# Switches_Leds.net
KiCad netlist of a schematic drawn in Altium Designer
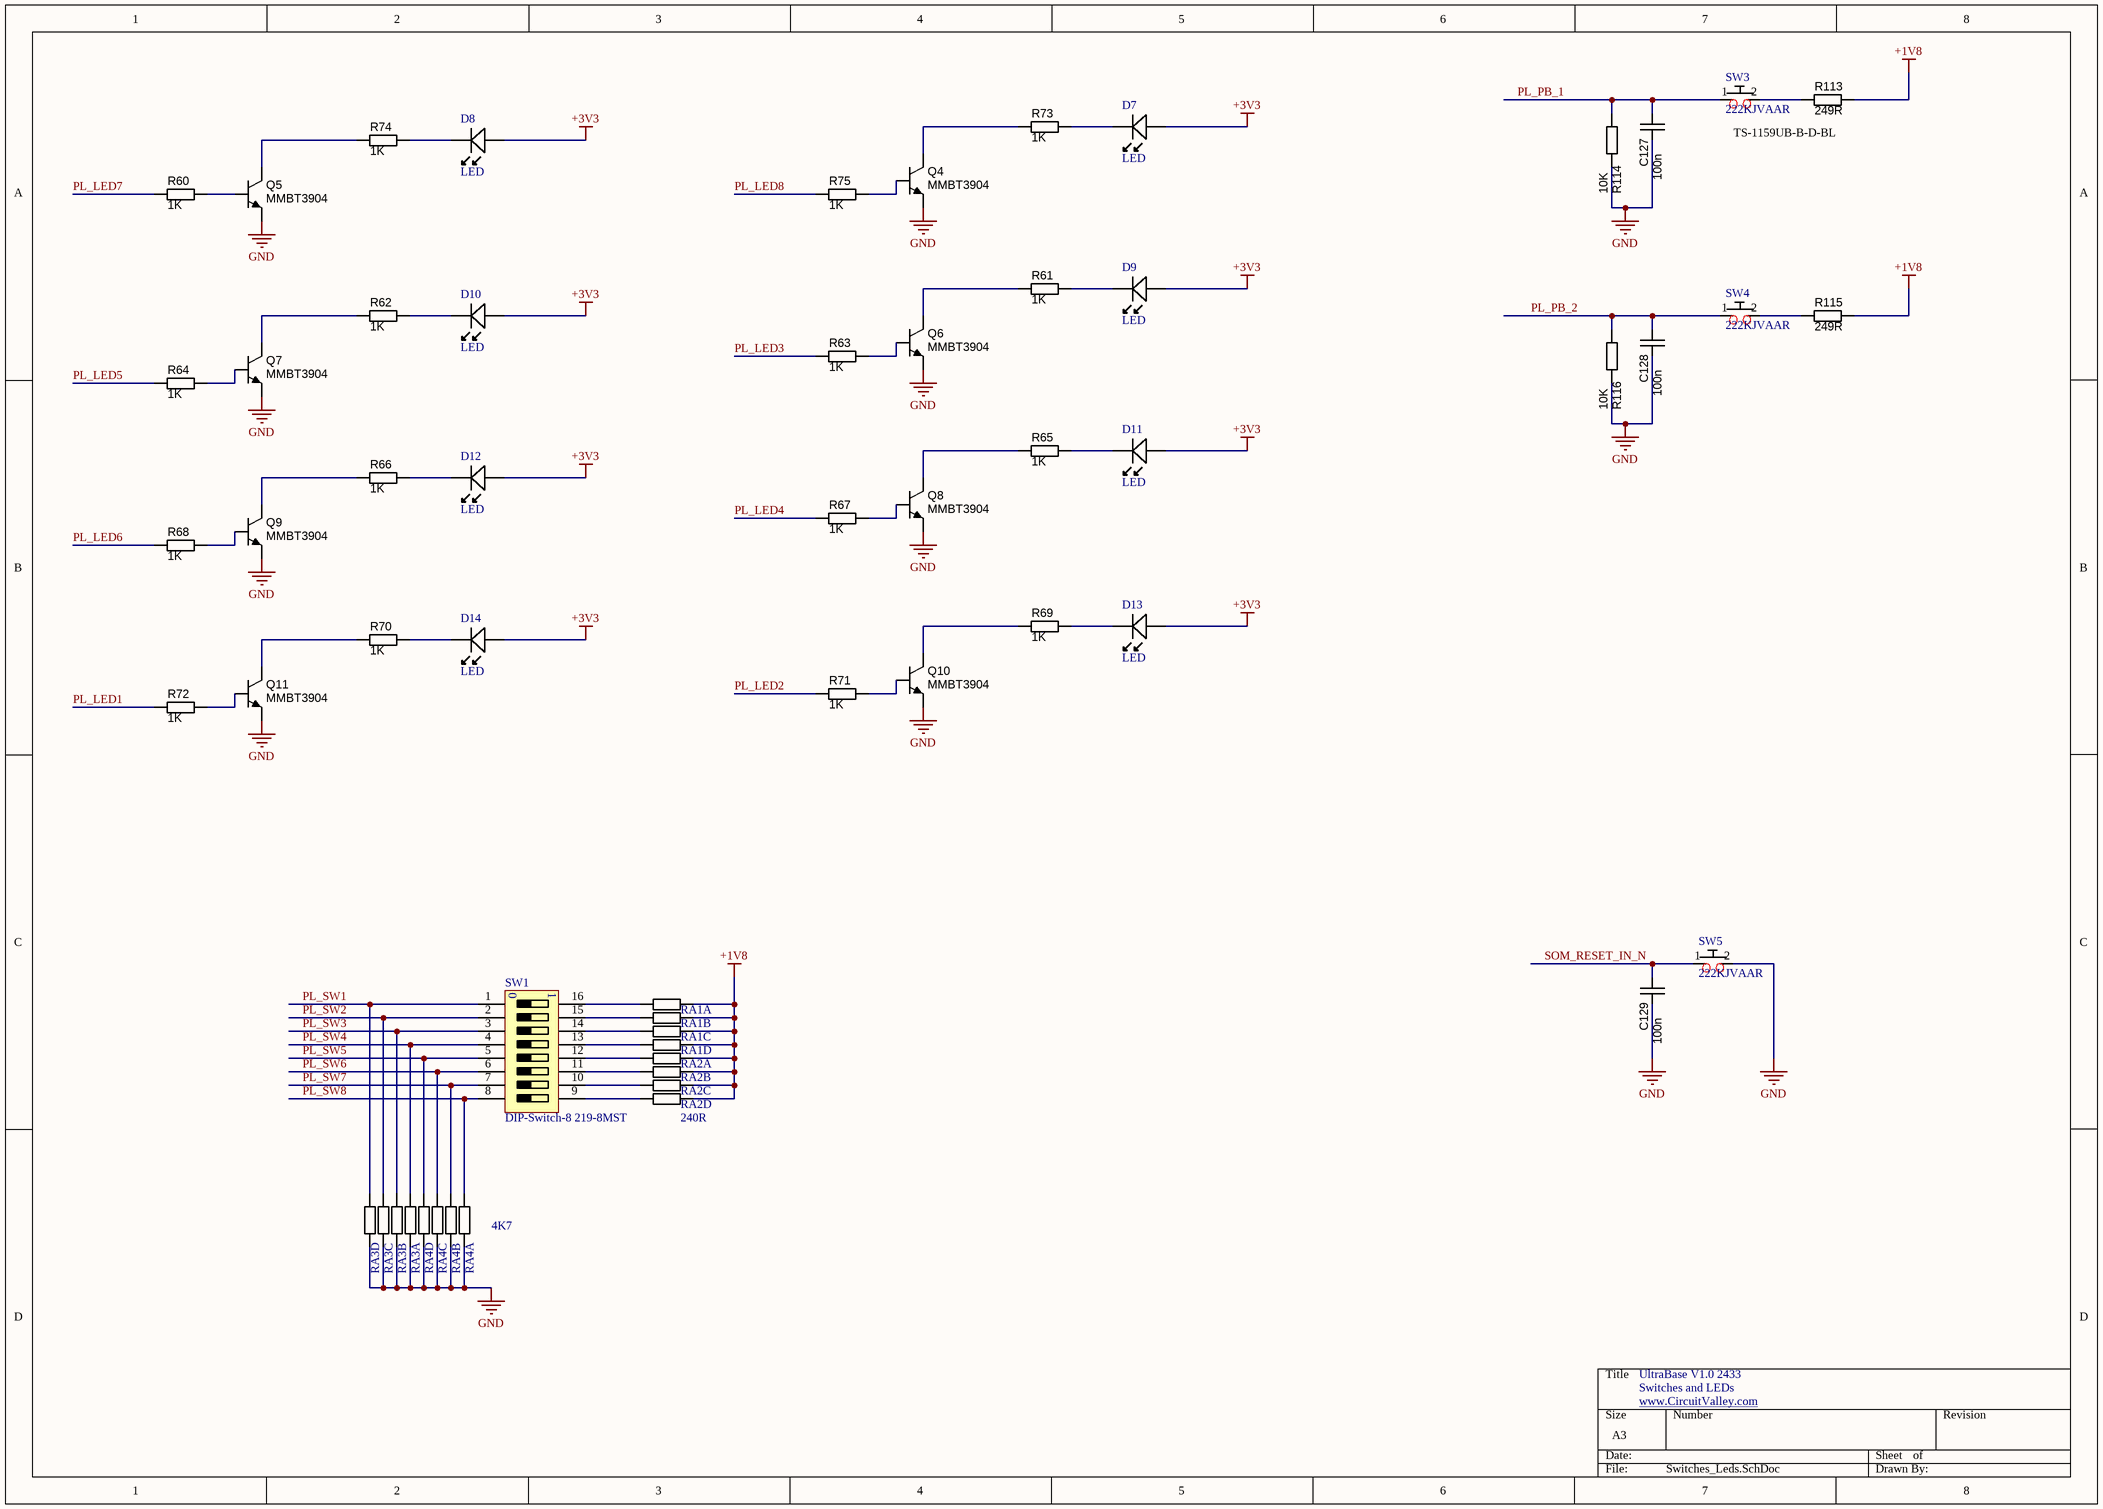
[diagram p0: Switches_Leds.SchDoc]

(export (version "E")
  (design (tool "Eeschema 10.0.6"))
  (components
    (comp (ref "C127")
      (value "100n")
      (footprint "CAPC1608N")
      (description "Capacitor SMD Cer 120pF 10% 50V C0G 0603")
      (fields (field (name "TOLERANCE") "±10%"))
      (libsource (lib "PBL - Capacitors") (part "CAPC_120p_0603_C0G_50V"))
    )
    (comp (ref "C128")
      (value "100n")
      (footprint "CAPC1608N")
      (description "Capacitor SMD Cer 120pF 10% 50V C0G 0603")
      (fields (field (name "TOLERANCE") "±10%"))
      (libsource (lib "PBL - Capacitors") (part "CAPC_120p_0603_C0G_50V"))
    )
    (comp (ref "C129")
      (value "100n")
      (footprint "CAPC1608N")
      (description "Capacitor SMD Cer 120pF 10% 50V C0G 0603")
      (fields (field (name "TOLERANCE") "±10%"))
      (libsource (lib "PBL - Capacitors") (part "CAPC_120p_0603_C0G_50V"))
    )
    (comp (ref "D7") (value "LED") (footprint "1206_LED") (libsource (lib "cvlib") (part "LED")))
    (comp (ref "D8") (value "LED") (footprint "1206_LED") (libsource (lib "cvlib") (part "LED")))
    (comp (ref "D9") (value "LED") (footprint "1206_LED") (libsource (lib "cvlib") (part "LED")))
    (comp (ref "D10") (value "LED") (footprint "1206_LED") (libsource (lib "cvlib") (part "LED")))
    (comp (ref "D11") (value "LED") (footprint "1206_LED") (libsource (lib "cvlib") (part "LED")))
    (comp (ref "D12") (value "LED") (footprint "1206_LED") (libsource (lib "cvlib") (part "LED")))
    (comp (ref "D13") (value "LED") (footprint "1206_LED") (libsource (lib "cvlib") (part "LED")))
    (comp (ref "D14") (value "LED") (footprint "1206_LED") (libsource (lib "cvlib") (part "LED")))
    (comp (ref "Q4")
      (value "NPN_MMBT3904")
      (footprint "SOT23-3")
      (description "Transistor SMD NPN 40V 0.2A 350mW SOT-23")
      (fields (field (name "MANUFACTURER PART NUMBER 1") "MMBT3904"))
      (libsource (lib "PBL - Transistors") (part "NPN_MMBT3904"))
    )
    (comp (ref "Q5")
      (value "NPN_MMBT3904")
      (footprint "SOT23-3")
      (description "Transistor SMD NPN 40V 0.2A 350mW SOT-23")
      (fields (field (name "MANUFACTURER PART NUMBER 1") "MMBT3904"))
      (libsource (lib "PBL - Transistors") (part "NPN_MMBT3904"))
    )
    (comp (ref "Q6")
      (value "NPN_MMBT3904")
      (footprint "SOT23-3")
      (description "Transistor SMD NPN 40V 0.2A 350mW SOT-23")
      (fields (field (name "MANUFACTURER PART NUMBER 1") "MMBT3904"))
      (libsource (lib "PBL - Transistors") (part "NPN_MMBT3904"))
    )
    (comp (ref "Q7")
      (value "NPN_MMBT3904")
      (footprint "SOT23-3")
      (description "Transistor SMD NPN 40V 0.2A 350mW SOT-23")
      (fields (field (name "MANUFACTURER PART NUMBER 1") "MMBT3904"))
      (libsource (lib "PBL - Transistors") (part "NPN_MMBT3904"))
    )
    (comp (ref "Q8")
      (value "NPN_MMBT3904")
      (footprint "SOT23-3")
      (description "Transistor SMD NPN 40V 0.2A 350mW SOT-23")
      (fields (field (name "MANUFACTURER PART NUMBER 1") "MMBT3904"))
      (libsource (lib "PBL - Transistors") (part "NPN_MMBT3904"))
    )
    (comp (ref "Q9")
      (value "NPN_MMBT3904")
      (footprint "SOT23-3")
      (description "Transistor SMD NPN 40V 0.2A 350mW SOT-23")
      (fields (field (name "MANUFACTURER PART NUMBER 1") "MMBT3904"))
      (libsource (lib "PBL - Transistors") (part "NPN_MMBT3904"))
    )
    (comp (ref "Q10")
      (value "NPN_MMBT3904")
      (footprint "SOT23-3")
      (description "Transistor SMD NPN 40V 0.2A 350mW SOT-23")
      (fields (field (name "MANUFACTURER PART NUMBER 1") "MMBT3904"))
      (libsource (lib "PBL - Transistors") (part "NPN_MMBT3904"))
    )
    (comp (ref "Q11")
      (value "NPN_MMBT3904")
      (footprint "SOT23-3")
      (description "Transistor SMD NPN 40V 0.2A 350mW SOT-23")
      (fields (field (name "MANUFACTURER PART NUMBER 1") "MMBT3904"))
      (libsource (lib "PBL - Transistors") (part "NPN_MMBT3904"))
    )
    (comp (ref "R60")
      (value "1K")
      (footprint "RESC1608N")
      (description "Resistor, SMD chip")
      (fields (field (name "TOLERANCE") "±5%") (field (name "Comment") "RES_NL_0603"))
      (libsource (lib "PBL - Resistors") (part "RES_NL_0603"))
    )
    (comp (ref "R61")
      (value "1K")
      (footprint "RESC1608N")
      (description "Resistor, SMD chip")
      (fields (field (name "TOLERANCE") "±5%") (field (name "Comment") "RES_NL_0603"))
      (libsource (lib "PBL - Resistors") (part "RES_NL_0603"))
    )
    (comp (ref "R62")
      (value "1K")
      (footprint "RESC1608N")
      (description "Resistor, SMD chip")
      (fields (field (name "TOLERANCE") "±5%") (field (name "Comment") "RES_NL_0603"))
      (libsource (lib "PBL - Resistors") (part "RES_NL_0603"))
    )
    (comp (ref "R63")
      (value "1K")
      (footprint "RESC1608N")
      (description "Resistor, SMD chip")
      (fields (field (name "TOLERANCE") "±5%") (field (name "Comment") "RES_NL_0603"))
      (libsource (lib "PBL - Resistors") (part "RES_NL_0603"))
    )
    (comp (ref "R64")
      (value "1K")
      (footprint "RESC1608N")
      (description "Resistor, SMD chip")
      (fields (field (name "TOLERANCE") "±5%") (field (name "Comment") "RES_NL_0603"))
      (libsource (lib "PBL - Resistors") (part "RES_NL_0603"))
    )
    (comp (ref "R65")
      (value "1K")
      (footprint "RESC1608N")
      (description "Resistor, SMD chip")
      (fields (field (name "TOLERANCE") "±5%") (field (name "Comment") "RES_NL_0603"))
      (libsource (lib "PBL - Resistors") (part "RES_NL_0603"))
    )
    (comp (ref "R66")
      (value "1K")
      (footprint "RESC1608N")
      (description "Resistor, SMD chip")
      (fields (field (name "TOLERANCE") "±5%") (field (name "Comment") "RES_NL_0603"))
      (libsource (lib "PBL - Resistors") (part "RES_NL_0603"))
    )
    (comp (ref "R67")
      (value "1K")
      (footprint "RESC1608N")
      (description "Resistor, SMD chip")
      (fields (field (name "TOLERANCE") "±5%") (field (name "Comment") "RES_NL_0603"))
      (libsource (lib "PBL - Resistors") (part "RES_NL_0603"))
    )
    (comp (ref "R68")
      (value "1K")
      (footprint "RESC1608N")
      (description "Resistor, SMD chip")
      (fields (field (name "TOLERANCE") "±5%") (field (name "Comment") "RES_NL_0603"))
      (libsource (lib "PBL - Resistors") (part "RES_NL_0603"))
    )
    (comp (ref "R69")
      (value "1K")
      (footprint "RESC1608N")
      (description "Resistor, SMD chip")
      (fields (field (name "TOLERANCE") "±5%") (field (name "Comment") "RES_NL_0603"))
      (libsource (lib "PBL - Resistors") (part "RES_NL_0603"))
    )
    (comp (ref "R70")
      (value "1K")
      (footprint "RESC1608N")
      (description "Resistor, SMD chip")
      (fields (field (name "TOLERANCE") "±5%") (field (name "Comment") "RES_NL_0603"))
      (libsource (lib "PBL - Resistors") (part "RES_NL_0603"))
    )
    (comp (ref "R71")
      (value "1K")
      (footprint "RESC1608N")
      (description "Resistor, SMD chip")
      (fields (field (name "TOLERANCE") "±5%") (field (name "Comment") "RES_NL_0603"))
      (libsource (lib "PBL - Resistors") (part "RES_NL_0603"))
    )
    (comp (ref "R72")
      (value "1K")
      (footprint "RESC1608N")
      (description "Resistor, SMD chip")
      (fields (field (name "TOLERANCE") "±5%") (field (name "Comment") "RES_NL_0603"))
      (libsource (lib "PBL - Resistors") (part "RES_NL_0603"))
    )
    (comp (ref "R73")
      (value "1K")
      (footprint "RESC1608N")
      (description "Resistor, SMD chip")
      (fields (field (name "TOLERANCE") "±5%") (field (name "Comment") "RES_NL_0603"))
      (libsource (lib "PBL - Resistors") (part "RES_NL_0603"))
    )
    (comp (ref "R74")
      (value "1K")
      (footprint "RESC1608N")
      (description "Resistor, SMD chip")
      (fields (field (name "TOLERANCE") "±5%") (field (name "Comment") "RES_NL_0603"))
      (libsource (lib "PBL - Resistors") (part "RES_NL_0603"))
    )
    (comp (ref "R75")
      (value "1K")
      (footprint "RESC1608N")
      (description "Resistor, SMD chip")
      (fields (field (name "TOLERANCE") "±5%") (field (name "Comment") "RES_NL_0603"))
      (libsource (lib "PBL - Resistors") (part "RES_NL_0603"))
    )
    (comp (ref "R113")
      (value "249R")
      (footprint "RESC1608N")
      (description "Resistor, SMD chip")
      (fields (field (name "TOLERANCE") "±5%") (field (name "Comment") "RES_NL_0603"))
      (libsource (lib "") (part "RES_NL_0603_1"))
    )
    (comp (ref "R114")
      (value "10K")
      (footprint "RESC1608N")
      (description "Resistor, SMD chip")
      (fields (field (name "TOLERANCE") "±5%") (field (name "Comment") "RES_NL_0603"))
      (libsource (lib "") (part "RES_NL_0603_2"))
    )
    (comp (ref "R115")
      (value "249R")
      (footprint "RESC1608N")
      (description "Resistor, SMD chip")
      (fields (field (name "TOLERANCE") "±5%") (field (name "Comment") "RES_NL_0603"))
      (libsource (lib "") (part "RES_NL_0603_1"))
    )
    (comp (ref "R116")
      (value "10K")
      (footprint "RESC1608N")
      (description "Resistor, SMD chip")
      (fields (field (name "TOLERANCE") "±5%") (field (name "Comment") "RES_NL_0603"))
      (libsource (lib "") (part "RES_NL_0603_2"))
    )
    (comp (ref "RA1")
      (value "Thick Film")
      (footprint "YC164")
      (description "Resistor array 4-pack 5% 0402 SMD")
      (libsource (lib "") (part "RES_ARRAY_0402_5%_1"))
    )
    (comp (ref "RA2")
      (value "Thick Film")
      (footprint "YC164")
      (description "Resistor array 4-pack 5% 0402 SMD")
      (libsource (lib "") (part "RES_ARRAY_0402_5%_1"))
    )
    (comp (ref "RA3")
      (value "Thick Film")
      (footprint "YC164")
      (description "Resistor array 4-pack 5% 0402 SMD")
      (libsource (lib "cvlib") (part "RES_ARRAY_0402_5%"))
    )
    (comp (ref "RA4")
      (value "Thick Film")
      (footprint "YC164")
      (description "Resistor array 4-pack 5% 0402 SMD")
      (libsource (lib "cvlib") (part "RES_ARRAY_0402_5%"))
    )
    (comp (ref "SW1")
      (value "DIP-Switch-8 219-8MST")
      (footprint "219-8MST")
      (description "DIP Switch 8 Position")
      (libsource (lib "cvlib") (part "DIP-Switch-8"))
    )
    (comp (ref "SW3")
      (value "222KJVAAR")
      (footprint "222KJVAAR")
      (libsource (lib "cvlib") (part "PushButton"))
    )
    (comp (ref "SW4")
      (value "222KJVAAR")
      (footprint "222KJVAAR")
      (libsource (lib "cvlib") (part "PushButton"))
    )
    (comp (ref "SW5")
      (value "222KJVAAR")
      (footprint "222KJVAAR")
      (libsource (lib "cvlib") (part "PushButton"))
    )
  )
  (nets
    (net (code "1") (name "+1V8") (class "Default")
      (node (ref "R113") (pin "1") (pinfunction "1_1") (pintype "passive"))
      (node (ref "R115") (pin "1") (pinfunction "1_1") (pintype "passive"))
      (node (ref "RA1") (pin "1") (pinfunction "1_1") (pintype "passive"))
      (node (ref "RA1") (pin "2") (pinfunction "2_2") (pintype "passive"))
      (node (ref "RA1") (pin "3") (pinfunction "3_3") (pintype "passive"))
      (node (ref "RA1") (pin "4") (pinfunction "4_4") (pintype "passive"))
      (node (ref "RA2") (pin "1") (pinfunction "1_1") (pintype "passive"))
      (node (ref "RA2") (pin "2") (pinfunction "2_2") (pintype "passive"))
      (node (ref "RA2") (pin "3") (pinfunction "3_3") (pintype "passive"))
      (node (ref "RA2") (pin "4") (pinfunction "4_4") (pintype "passive"))
    )
    (net (code "2") (name "+3V3") (class "Default")
      (node (ref "D10") (pin "A") (pinfunction "A_A") (pintype "passive"))
      (node (ref "D11") (pin "A") (pinfunction "A_A") (pintype "passive"))
      (node (ref "D12") (pin "A") (pinfunction "A_A") (pintype "passive"))
      (node (ref "D13") (pin "A") (pinfunction "A_A") (pintype "passive"))
      (node (ref "D14") (pin "A") (pinfunction "A_A") (pintype "passive"))
      (node (ref "D7") (pin "A") (pinfunction "A_A") (pintype "passive"))
      (node (ref "D8") (pin "A") (pinfunction "A_A") (pintype "passive"))
      (node (ref "D9") (pin "A") (pinfunction "A_A") (pintype "passive"))
    )
    (net (code "3") (name "/PL_LED1") (class "Default")
      (node (ref "R72") (pin "1") (pinfunction "1_1") (pintype "passive"))
    )
    (net (code "4") (name "/PL_LED2") (class "Default")
      (node (ref "R71") (pin "1") (pinfunction "1_1") (pintype "passive"))
    )
    (net (code "5") (name "/PL_LED3") (class "Default")
      (node (ref "R63") (pin "1") (pinfunction "1_1") (pintype "passive"))
    )
    (net (code "6") (name "/PL_LED4") (class "Default")
      (node (ref "R67") (pin "1") (pinfunction "1_1") (pintype "passive"))
    )
    (net (code "7") (name "/PL_LED5") (class "Default")
      (node (ref "R64") (pin "1") (pinfunction "1_1") (pintype "passive"))
    )
    (net (code "8") (name "/PL_LED6") (class "Default")
      (node (ref "R68") (pin "1") (pinfunction "1_1") (pintype "passive"))
    )
    (net (code "9") (name "/PL_LED7") (class "Default")
      (node (ref "R60") (pin "1") (pinfunction "1_1") (pintype "passive"))
    )
    (net (code "10") (name "/PL_LED8") (class "Default")
      (node (ref "R75") (pin "1") (pinfunction "1_1") (pintype "passive"))
    )
    (net (code "11") (name "/PL_PB_1") (class "Default")
      (node (ref "C127") (pin "1") (pintype "passive"))
      (node (ref "R114") (pin "2") (pinfunction "2_2") (pintype "passive"))
      (node (ref "SW3") (pin "1") (pinfunction "P1_1") (pintype "passive"))
    )
    (net (code "12") (name "/PL_PB_2") (class "Default")
      (node (ref "C128") (pin "1") (pintype "passive"))
      (node (ref "R116") (pin "2") (pinfunction "2_2") (pintype "passive"))
      (node (ref "SW4") (pin "1") (pinfunction "P1_1") (pintype "passive"))
    )
    (net (code "13") (name "/PL_SW1") (class "Default")
      (node (ref "RA3") (pin "5") (pinfunction "5_5") (pintype "passive"))
      (node (ref "SW1") (pin "1") (pinfunction "1_1") (pintype "passive"))
    )
    (net (code "14") (name "/PL_SW2") (class "Default")
      (node (ref "RA3") (pin "6") (pinfunction "6_6") (pintype "passive"))
      (node (ref "SW1") (pin "2") (pinfunction "2_2") (pintype "passive"))
    )
    (net (code "15") (name "/PL_SW3") (class "Default")
      (node (ref "RA3") (pin "7") (pinfunction "7_7") (pintype "passive"))
      (node (ref "SW1") (pin "3") (pinfunction "3_3") (pintype "passive"))
    )
    (net (code "16") (name "/PL_SW4") (class "Default")
      (node (ref "RA3") (pin "8") (pinfunction "8_8") (pintype "passive"))
      (node (ref "SW1") (pin "4") (pinfunction "4_4") (pintype "passive"))
    )
    (net (code "17") (name "/PL_SW5") (class "Default")
      (node (ref "RA4") (pin "5") (pinfunction "5_5") (pintype "passive"))
      (node (ref "SW1") (pin "5") (pinfunction "5_5") (pintype "passive"))
    )
    (net (code "18") (name "/PL_SW6") (class "Default")
      (node (ref "RA4") (pin "6") (pinfunction "6_6") (pintype "passive"))
      (node (ref "SW1") (pin "6") (pinfunction "6_6") (pintype "passive"))
    )
    (net (code "19") (name "/PL_SW7") (class "Default")
      (node (ref "RA4") (pin "7") (pinfunction "7_7") (pintype "passive"))
      (node (ref "SW1") (pin "7") (pinfunction "7_7") (pintype "passive"))
    )
    (net (code "20") (name "/PL_SW8") (class "Default")
      (node (ref "RA4") (pin "8") (pinfunction "8_8") (pintype "passive"))
      (node (ref "SW1") (pin "8") (pinfunction "8_8") (pintype "passive"))
    )
    (net (code "21") (name "/SOM_RESET_IN_N") (class "Default")
      (node (ref "C129") (pin "1") (pintype "passive"))
      (node (ref "SW5") (pin "1") (pinfunction "P1_1") (pintype "passive"))
    )
    (net (code "22") (name "GND") (class "Default")
      (node (ref "C127") (pin "2") (pintype "passive"))
      (node (ref "C128") (pin "2") (pintype "passive"))
      (node (ref "C129") (pin "2") (pintype "passive"))
      (node (ref "Q10") (pin "2") (pinfunction "E_2") (pintype "passive"))
      (node (ref "Q11") (pin "2") (pinfunction "E_2") (pintype "passive"))
      (node (ref "Q4") (pin "2") (pinfunction "E_2") (pintype "passive"))
      (node (ref "Q5") (pin "2") (pinfunction "E_2") (pintype "passive"))
      (node (ref "Q6") (pin "2") (pinfunction "E_2") (pintype "passive"))
      (node (ref "Q7") (pin "2") (pinfunction "E_2") (pintype "passive"))
      (node (ref "Q8") (pin "2") (pinfunction "E_2") (pintype "passive"))
      (node (ref "Q9") (pin "2") (pinfunction "E_2") (pintype "passive"))
      (node (ref "R114") (pin "1") (pinfunction "1_1") (pintype "passive"))
      (node (ref "R116") (pin "1") (pinfunction "1_1") (pintype "passive"))
      (node (ref "RA3") (pin "1") (pinfunction "1_1") (pintype "passive"))
      (node (ref "RA3") (pin "2") (pinfunction "2_2") (pintype "passive"))
      (node (ref "RA3") (pin "3") (pinfunction "3_3") (pintype "passive"))
      (node (ref "RA3") (pin "4") (pinfunction "4_4") (pintype "passive"))
      (node (ref "RA4") (pin "1") (pinfunction "1_1") (pintype "passive"))
      (node (ref "RA4") (pin "2") (pinfunction "2_2") (pintype "passive"))
      (node (ref "RA4") (pin "3") (pinfunction "3_3") (pintype "passive"))
      (node (ref "RA4") (pin "4") (pinfunction "4_4") (pintype "passive"))
      (node (ref "SW5") (pin "2") (pinfunction "P2_2") (pintype "passive"))
    )
    (net (code "23") (name "Net-(D7-PadK)") (class "Default")
      (node (ref "D7") (pin "K") (pinfunction "K_K") (pintype "passive"))
      (node (ref "R73") (pin "2") (pinfunction "2_2") (pintype "passive"))
    )
    (net (code "24") (name "Net-(D8-PadK)") (class "Default")
      (node (ref "D8") (pin "K") (pinfunction "K_K") (pintype "passive"))
      (node (ref "R74") (pin "2") (pinfunction "2_2") (pintype "passive"))
    )
    (net (code "25") (name "Net-(D9-PadK)") (class "Default")
      (node (ref "D9") (pin "K") (pinfunction "K_K") (pintype "passive"))
      (node (ref "R61") (pin "2") (pinfunction "2_2") (pintype "passive"))
    )
    (net (code "26") (name "Net-(D10-PadK)") (class "Default")
      (node (ref "D10") (pin "K") (pinfunction "K_K") (pintype "passive"))
      (node (ref "R62") (pin "2") (pinfunction "2_2") (pintype "passive"))
    )
    (net (code "27") (name "Net-(D11-PadK)") (class "Default")
      (node (ref "D11") (pin "K") (pinfunction "K_K") (pintype "passive"))
      (node (ref "R65") (pin "2") (pinfunction "2_2") (pintype "passive"))
    )
    (net (code "28") (name "Net-(D12-PadK)") (class "Default")
      (node (ref "D12") (pin "K") (pinfunction "K_K") (pintype "passive"))
      (node (ref "R66") (pin "2") (pinfunction "2_2") (pintype "passive"))
    )
    (net (code "29") (name "Net-(D13-PadK)") (class "Default")
      (node (ref "D13") (pin "K") (pinfunction "K_K") (pintype "passive"))
      (node (ref "R69") (pin "2") (pinfunction "2_2") (pintype "passive"))
    )
    (net (code "30") (name "Net-(D14-PadK)") (class "Default")
      (node (ref "D14") (pin "K") (pinfunction "K_K") (pintype "passive"))
      (node (ref "R70") (pin "2") (pinfunction "2_2") (pintype "passive"))
    )
    (net (code "31") (name "Net-(Q4-B)") (class "Default")
      (node (ref "Q4") (pin "1") (pinfunction "B_1") (pintype "passive"))
      (node (ref "R75") (pin "2") (pinfunction "2_2") (pintype "passive"))
    )
    (net (code "32") (name "Net-(Q4-C)") (class "Default")
      (node (ref "Q4") (pin "3") (pinfunction "C_3") (pintype "passive"))
      (node (ref "R73") (pin "1") (pinfunction "1_1") (pintype "passive"))
    )
    (net (code "33") (name "Net-(Q5-B)") (class "Default")
      (node (ref "Q5") (pin "1") (pinfunction "B_1") (pintype "passive"))
      (node (ref "R60") (pin "2") (pinfunction "2_2") (pintype "passive"))
    )
    (net (code "34") (name "Net-(Q5-C)") (class "Default")
      (node (ref "Q5") (pin "3") (pinfunction "C_3") (pintype "passive"))
      (node (ref "R74") (pin "1") (pinfunction "1_1") (pintype "passive"))
    )
    (net (code "35") (name "Net-(Q6-B)") (class "Default")
      (node (ref "Q6") (pin "1") (pinfunction "B_1") (pintype "passive"))
      (node (ref "R63") (pin "2") (pinfunction "2_2") (pintype "passive"))
    )
    (net (code "36") (name "Net-(Q6-C)") (class "Default")
      (node (ref "Q6") (pin "3") (pinfunction "C_3") (pintype "passive"))
      (node (ref "R61") (pin "1") (pinfunction "1_1") (pintype "passive"))
    )
    (net (code "37") (name "Net-(Q7-B)") (class "Default")
      (node (ref "Q7") (pin "1") (pinfunction "B_1") (pintype "passive"))
      (node (ref "R64") (pin "2") (pinfunction "2_2") (pintype "passive"))
    )
    (net (code "38") (name "Net-(Q7-C)") (class "Default")
      (node (ref "Q7") (pin "3") (pinfunction "C_3") (pintype "passive"))
      (node (ref "R62") (pin "1") (pinfunction "1_1") (pintype "passive"))
    )
    (net (code "39") (name "Net-(Q8-B)") (class "Default")
      (node (ref "Q8") (pin "1") (pinfunction "B_1") (pintype "passive"))
      (node (ref "R67") (pin "2") (pinfunction "2_2") (pintype "passive"))
    )
    (net (code "40") (name "Net-(Q8-C)") (class "Default")
      (node (ref "Q8") (pin "3") (pinfunction "C_3") (pintype "passive"))
      (node (ref "R65") (pin "1") (pinfunction "1_1") (pintype "passive"))
    )
    (net (code "41") (name "Net-(Q9-B)") (class "Default")
      (node (ref "Q9") (pin "1") (pinfunction "B_1") (pintype "passive"))
      (node (ref "R68") (pin "2") (pinfunction "2_2") (pintype "passive"))
    )
    (net (code "42") (name "Net-(Q9-C)") (class "Default")
      (node (ref "Q9") (pin "3") (pinfunction "C_3") (pintype "passive"))
      (node (ref "R66") (pin "1") (pinfunction "1_1") (pintype "passive"))
    )
    (net (code "43") (name "Net-(Q10-B)") (class "Default")
      (node (ref "Q10") (pin "1") (pinfunction "B_1") (pintype "passive"))
      (node (ref "R71") (pin "2") (pinfunction "2_2") (pintype "passive"))
    )
    (net (code "44") (name "Net-(Q10-C)") (class "Default")
      (node (ref "Q10") (pin "3") (pinfunction "C_3") (pintype "passive"))
      (node (ref "R69") (pin "1") (pinfunction "1_1") (pintype "passive"))
    )
    (net (code "45") (name "Net-(Q11-B)") (class "Default")
      (node (ref "Q11") (pin "1") (pinfunction "B_1") (pintype "passive"))
      (node (ref "R72") (pin "2") (pinfunction "2_2") (pintype "passive"))
    )
    (net (code "46") (name "Net-(Q11-C)") (class "Default")
      (node (ref "Q11") (pin "3") (pinfunction "C_3") (pintype "passive"))
      (node (ref "R70") (pin "1") (pinfunction "1_1") (pintype "passive"))
    )
    (net (code "47") (name "Net-(RA1-Pad5)") (class "Default")
      (node (ref "RA1") (pin "5") (pinfunction "5_5") (pintype "passive"))
      (node (ref "SW1") (pin "13") (pinfunction "13_13") (pintype "passive"))
    )
    (net (code "48") (name "Net-(RA1-Pad6)") (class "Default")
      (node (ref "RA1") (pin "6") (pinfunction "6_6") (pintype "passive"))
      (node (ref "SW1") (pin "14") (pinfunction "14_14") (pintype "passive"))
    )
    (net (code "49") (name "Net-(RA1-Pad7)") (class "Default")
      (node (ref "RA1") (pin "7") (pinfunction "7_7") (pintype "passive"))
      (node (ref "SW1") (pin "15") (pinfunction "15_15") (pintype "passive"))
    )
    (net (code "50") (name "Net-(RA1-Pad8)") (class "Default")
      (node (ref "RA1") (pin "8") (pinfunction "8_8") (pintype "passive"))
      (node (ref "SW1") (pin "16") (pinfunction "16_16") (pintype "passive"))
    )
    (net (code "51") (name "Net-(RA2-Pad5)") (class "Default")
      (node (ref "RA2") (pin "5") (pinfunction "5_5") (pintype "passive"))
      (node (ref "SW1") (pin "9") (pinfunction "9_9") (pintype "passive"))
    )
    (net (code "52") (name "Net-(RA2-Pad6)") (class "Default")
      (node (ref "RA2") (pin "6") (pinfunction "6_6") (pintype "passive"))
      (node (ref "SW1") (pin "10") (pinfunction "10_10") (pintype "passive"))
    )
    (net (code "53") (name "Net-(RA2-Pad7)") (class "Default")
      (node (ref "RA2") (pin "7") (pinfunction "7_7") (pintype "passive"))
      (node (ref "SW1") (pin "11") (pinfunction "11_11") (pintype "passive"))
    )
    (net (code "54") (name "Net-(RA2-Pad8)") (class "Default")
      (node (ref "RA2") (pin "8") (pinfunction "8_8") (pintype "passive"))
      (node (ref "SW1") (pin "12") (pinfunction "12_12") (pintype "passive"))
    )
    (net (code "55") (name "Net-(SW3-P2)") (class "Default")
      (node (ref "R113") (pin "2") (pinfunction "2_2") (pintype "passive"))
      (node (ref "SW3") (pin "2") (pinfunction "P2_2") (pintype "passive"))
    )
    (net (code "56") (name "Net-(SW4-P2)") (class "Default")
      (node (ref "R115") (pin "2") (pinfunction "2_2") (pintype "passive"))
      (node (ref "SW4") (pin "2") (pinfunction "P2_2") (pintype "passive"))
    )
  )
)
